# Buck_converter12_3_3V.net
KiCad netlist of a schematic drawn in Altium Designer
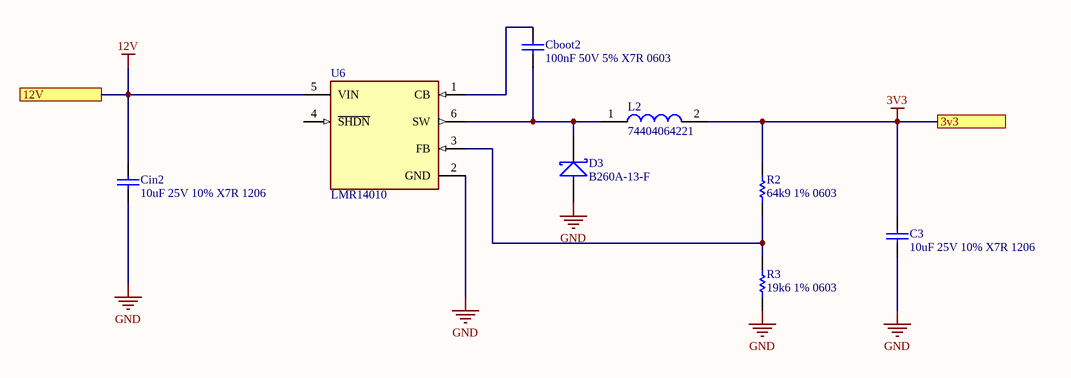
[diagram p0: Buck_converter12_3.3V.SchDoc]

(export (version "E")
  (design (tool "Eeschema 10.0.6"))
  (components
    (comp (ref "C3")
      (value "10uF 25V 10% X7R 1206")
      (footprint "Cap_Ceramic_1206")
      (description "Capacitor, Ceramic, SMD, 10uF, 25V, 10%, X7R, 1206")
      (libsource (lib "StandardCapacitors") (part "10uF 25V 10% X7R 1206"))
    )
    (comp (ref "Cboot2")
      (value "100nF 50V 5% X7R 0603")
      (footprint "Cap_Ceramic_0603")
      (description "Capacitor, Ceramic, SMD, 100nF, 50V, 5%, X7R, 0603")
      (libsource (lib "StandardCapacitors") (part "100nF 50V 5% X7R 0603"))
    )
    (comp (ref "Cin2")
      (value "10uF 25V 10% X7R 1206")
      (footprint "Cap_Ceramic_1206")
      (description "Capacitor, Ceramic, SMD, 10uF, 25V, 10%, X7R, 1206")
      (libsource (lib "StandardCapacitors") (part "10uF 25V 10% X7R 1206"))
    )
    (comp (ref "D3")
      (value "B260A-13-F")
      (footprint "SMA")
      (description "Diode, Schottky Barrier Rectifier, 60 V, 2 A, B260A-13-F")
      (libsource (lib "QUTMS_DiodeLibrary") (part "B260A-13-F"))
    )
    (comp (ref "L2")
      (value "74404064221")
      (footprint "Inductor_6x6mm")
      (description "FIXED IND 220UH 660MA 850 MOHM")
      (libsource (lib "QUTMS_InductorLibrary") (part "74404064221"))
    )
    (comp (ref "R2")
      (value "64k9 1% 0603")
      (footprint "Res_ThinFilm_0603")
      (description "Resistor, SMD, 64k9, 0.1W, 5%, 0603")
      (libsource (lib "QUTMS-MCISOLibrary") (part "64k9 1% 0603"))
    )
    (comp (ref "R3")
      (value "19k6 1% 0603")
      (footprint "Res_ThinFilm_0603")
      (description "Resistor, SMD, 19k6, 0.1W, 5%, 0603")
      (libsource (lib "QUTMS-MCISOLibrary") (part "19k6 1% 0603"))
    )
    (comp (ref "U6")
      (value "LMR14010")
      (footprint "LMR14010")
      (libsource (lib "QUTMS_PowerSupplyLibrary") (part "LMR14010"))
    )
  )
  (nets
    (net (code "1") (name "3V3") (class "Default")
      (node (ref "C3") (pin "2") (pinfunction "2_2") (pintype "passive"))
      (node (ref "L2") (pin "2") (pinfunction "2_2") (pintype "passive"))
      (node (ref "R2") (pin "2") (pinfunction "2_2") (pintype "passive"))
    )
    (net (code "2") (name "12V") (class "Default")
      (node (ref "Cin2") (pin "2") (pinfunction "2_2") (pintype "passive"))
      (node (ref "U6") (pin "5") (pinfunction "VIN_5") (pintype "power_in"))
    )
    (net (code "3") (name "GND") (class "Default")
      (node (ref "C3") (pin "1") (pinfunction "1_1") (pintype "passive"))
      (node (ref "Cin2") (pin "1") (pinfunction "1_1") (pintype "passive"))
      (node (ref "D3") (pin "A") (pinfunction "A_A") (pintype "passive"))
      (node (ref "R3") (pin "1") (pinfunction "1_1") (pintype "passive"))
      (node (ref "U6") (pin "2") (pinfunction "GND_2") (pintype "power_in"))
    )
    (net (code "4") (name "Net-(U6-CB)") (class "Default")
      (node (ref "Cboot2") (pin "2") (pinfunction "2_2") (pintype "passive"))
      (node (ref "U6") (pin "1") (pinfunction "CB_1") (pintype "input"))
    )
    (net (code "5") (name "Net-(U6-FB)") (class "Default")
      (node (ref "R2") (pin "1") (pinfunction "1_1") (pintype "passive"))
      (node (ref "R3") (pin "2") (pinfunction "2_2") (pintype "passive"))
      (node (ref "U6") (pin "3") (pinfunction "FB_3") (pintype "input"))
    )
    (net (code "6") (name "Net-(U6-SW)") (class "Default")
      (node (ref "Cboot2") (pin "1") (pinfunction "1_1") (pintype "passive"))
      (node (ref "D3") (pin "K") (pinfunction "K_K") (pintype "passive"))
      (node (ref "L2") (pin "1") (pinfunction "1_1") (pintype "passive"))
      (node (ref "U6") (pin "6") (pinfunction "SW_6") (pintype "output"))
    )
    (net (code "7") (name "unconnected-(U6-~{SHDN}-Pad4)") (class "Default")
      (node (ref "U6") (pin "4") (pinfunction "~{SHDN}_4") (pintype "input"))
    )
  )
)
